# MotorControllerVersion2.net
KiCad netlist of a schematic drawn in EAGLE
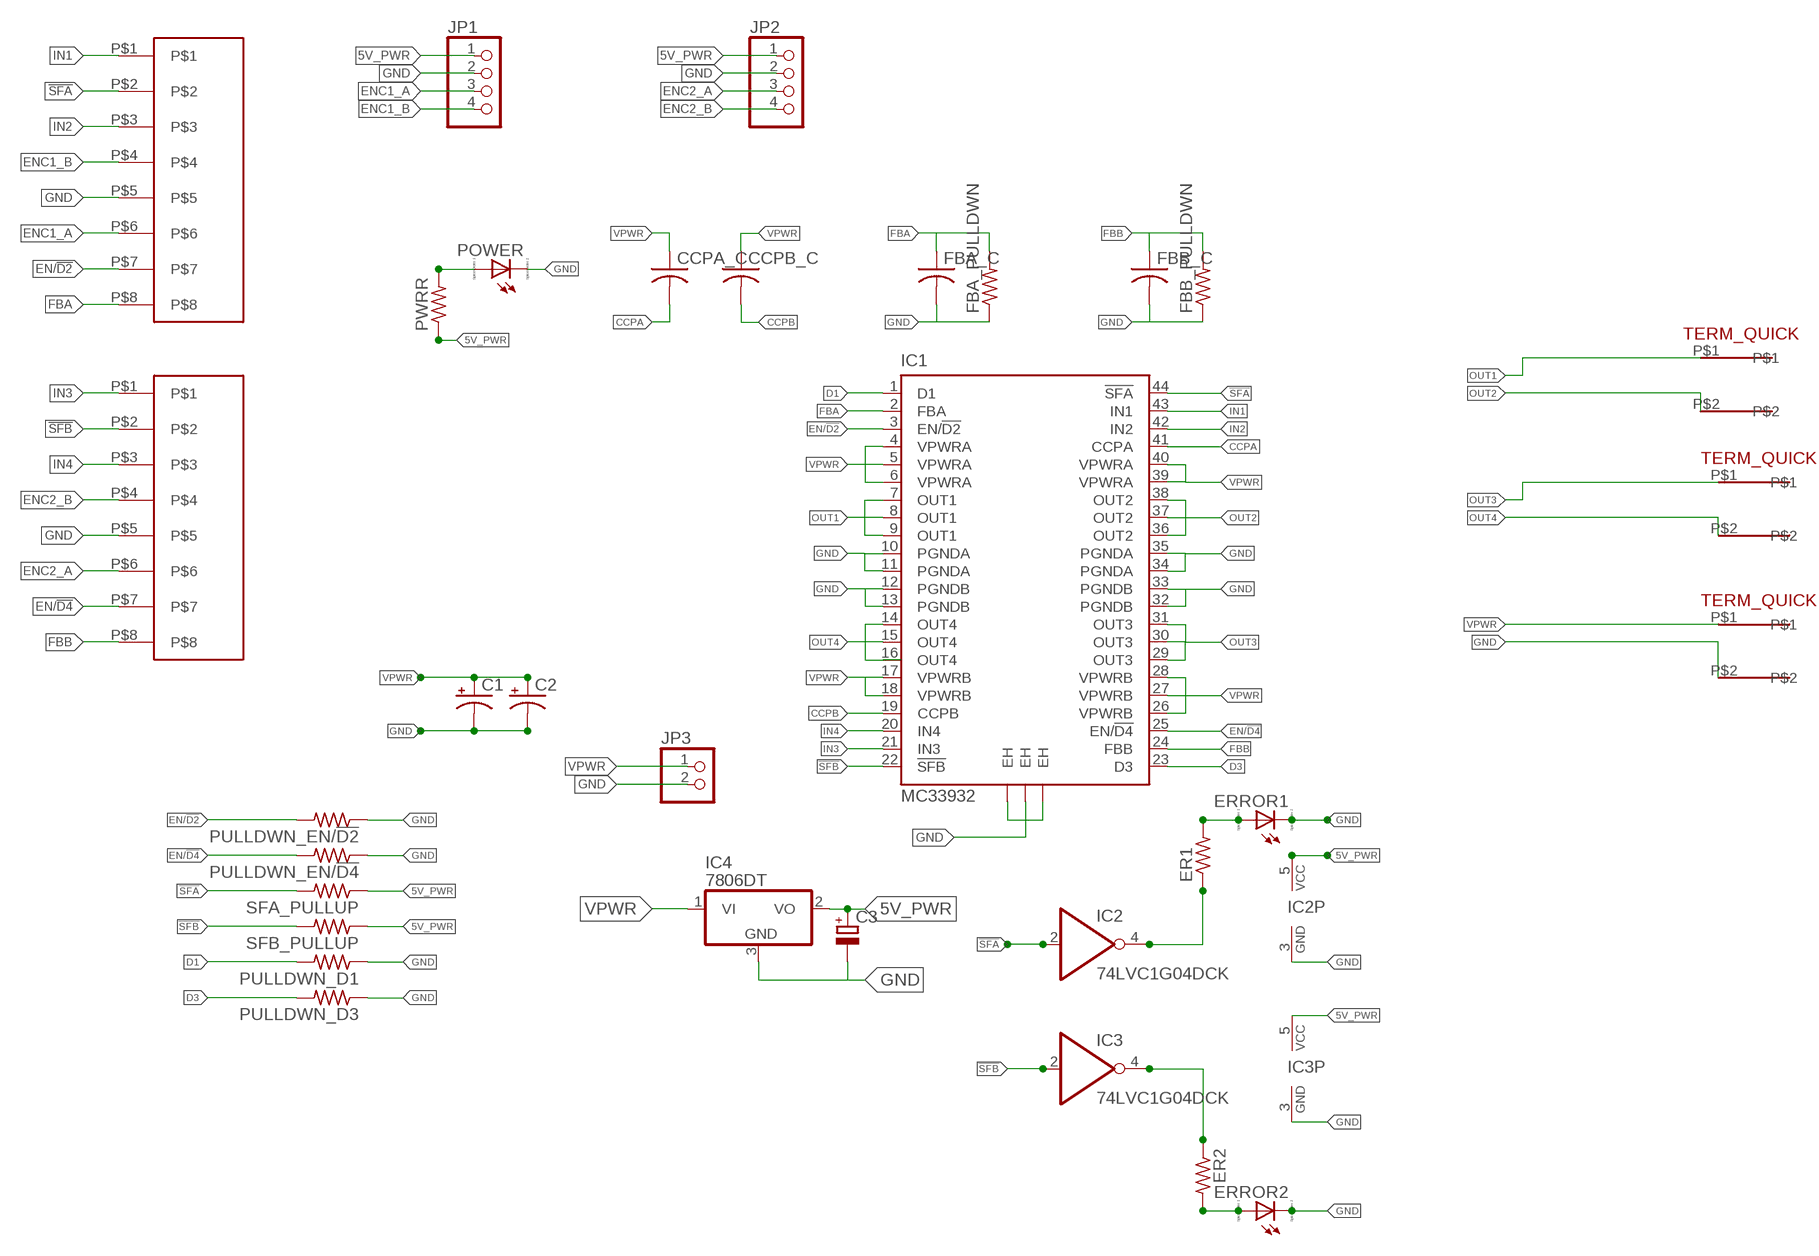
[diagram p0: schematic, sheet 1]

(export (version "E")
  (design (tool "Eeschema 10.0.6"))
  (components
    (comp (ref "C1")
      (value "CPOL-US153CLV-0810")
      (footprint "eagle-import:153CLV-0810")
      (libsource (lib "eagle-import") (part "CPOL-US153CLV-0810"))
    )
    (comp (ref "C2")
      (value "CPOL-US153CLV-0810")
      (footprint "eagle-import:153CLV-0810")
      (libsource (lib "eagle-import") (part "CPOL-US153CLV-0810"))
    )
    (comp (ref "C3")
      (value "CPOL-EU153CLV-0405")
      (footprint "eagle-import:153CLV-0405")
      (libsource (lib "eagle-import") (part "CPOL-EU153CLV-0405"))
    )
    (comp (ref "CCPA_C")
      (value "C-USC0805")
      (footprint "eagle-import:C0805")
      (libsource (lib "eagle-import") (part "C-USC0805"))
    )
    (comp (ref "CCPB_C")
      (value "C-USC0805")
      (footprint "eagle-import:C0805")
      (libsource (lib "eagle-import") (part "C-USC0805"))
    )
    (comp (ref "ER1")
      (value "R-US_R0805")
      (footprint "eagle-import:R0805")
      (libsource (lib "eagle-import") (part "R-US_R0805"))
    )
    (comp (ref "ER2")
      (value "R-US_R0805")
      (footprint "eagle-import:R0805")
      (libsource (lib "eagle-import") (part "R-US_R0805"))
    )
    (comp (ref "ERROR1")
      (value "LED_E")
      (footprint "eagle-import:LED_1206")
      (libsource (lib "eagle-import") (part "LED_E"))
    )
    (comp (ref "ERROR2")
      (value "LED_E")
      (footprint "eagle-import:LED_1206")
      (libsource (lib "eagle-import") (part "LED_E"))
    )
    (comp (ref "FBA_C")
      (value "C-USC0805")
      (footprint "eagle-import:C0805")
      (libsource (lib "eagle-import") (part "C-USC0805"))
    )
    (comp (ref "FBA_PULLDWN")
      (value "R-US_R0805")
      (footprint "eagle-import:R0805")
      (libsource (lib "eagle-import") (part "R-US_R0805"))
    )
    (comp (ref "FBB_C")
      (value "C-USC0805")
      (footprint "eagle-import:C0805")
      (libsource (lib "eagle-import") (part "C-USC0805"))
    )
    (comp (ref "FBB_PULLDWN")
      (value "R-US_R0805")
      (footprint "eagle-import:R0805")
      (libsource (lib "eagle-import") (part "R-US_R0805"))
    )
    (comp (ref "IC1")
      (value "MC33932")
      (footprint "eagle-import:HSOP44")
      (fields (field (name "MPN") "MC33932VW"))
      (libsource (lib "eagle-import") (part "MC33932"))
    )
    (comp (ref "IC2")
      (value "74LVC1G04DCK")
      (footprint "eagle-import:SC70-5")
      (libsource (lib "eagle-import") (part "741G04DCKLVC"))
    )
    (comp (ref "IC3")
      (value "74LVC1G04DCK")
      (footprint "eagle-import:SC70-5")
      (libsource (lib "eagle-import") (part "741G04DCKLVC"))
    )
    (comp (ref "IC4")
      (value "7806DT")
      (footprint "eagle-import:TO252")
      (libsource (lib "eagle-import") (part "78DT06"))
    )
    (comp (ref "JP1")
      (value "PINHD-1X4")
      (footprint "eagle-import:1X04")
      (libsource (lib "eagle-import") (part "PINHD-1X4"))
    )
    (comp (ref "JP2")
      (value "PINHD-1X4")
      (footprint "eagle-import:1X04")
      (libsource (lib "eagle-import") (part "PINHD-1X4"))
    )
    (comp (ref "JP3")
      (value "PINHD-1X2")
      (footprint "eagle-import:1X02")
      (libsource (lib "eagle-import") (part "PINHD-1X2"))
    )
    (comp (ref "POWER")
      (value "LED_E")
      (footprint "eagle-import:LED_1206")
      (libsource (lib "eagle-import") (part "LED_E"))
    )
    (comp (ref "PULLDWN_D1")
      (value "R-US_R0805")
      (footprint "eagle-import:R0805")
      (libsource (lib "eagle-import") (part "R-US_R0805"))
    )
    (comp (ref "PULLDWN_D3")
      (value "R-US_R0805")
      (footprint "eagle-import:R0805")
      (libsource (lib "eagle-import") (part "R-US_R0805"))
    )
    (comp (ref "PULLDWN_EN/!D2")
      (value "R-US_R0805")
      (footprint "eagle-import:R0805")
      (libsource (lib "eagle-import") (part "R-US_R0805"))
    )
    (comp (ref "PULLDWN_EN/!D4")
      (value "R-US_R0805")
      (footprint "eagle-import:R0805")
      (libsource (lib "eagle-import") (part "R-US_R0805"))
    )
    (comp (ref "PWRR")
      (value "R-US_R0805")
      (footprint "eagle-import:R0805")
      (libsource (lib "eagle-import") (part "R-US_R0805"))
    )
    (comp (ref "SFA_PULLUP")
      (value "R-US_R0805")
      (footprint "eagle-import:R0805")
      (libsource (lib "eagle-import") (part "R-US_R0805"))
    )
    (comp (ref "SFB_PULLUP")
      (value "R-US_R0805")
      (footprint "eagle-import:R0805")
      (libsource (lib "eagle-import") (part "R-US_R0805"))
    )
    (comp (ref "U$1")
      (value "ETHERNETPORT")
      (footprint "eagle-import:ETHERNETPORT")
      (libsource (lib "eagle-import") (part "ETHERNETPORT"))
    )
    (comp (ref "U$2")
      (value "ETHERNETPORT")
      (footprint "eagle-import:ETHERNETPORT")
      (libsource (lib "eagle-import") (part "ETHERNETPORT"))
    )
    (comp (ref "U$3")
      (value "TERM_QUICK")
      (footprint "eagle-import:TERM_QUICK")
      (libsource (lib "eagle-import") (part "TERM_QUICK"))
    )
    (comp (ref "U$4")
      (value "TERM_QUICK")
      (footprint "eagle-import:TERM_QUICK")
      (libsource (lib "eagle-import") (part "TERM_QUICK"))
    )
    (comp (ref "U$5")
      (value "TERM_QUICK")
      (footprint "eagle-import:TERM_QUICK")
      (libsource (lib "eagle-import") (part "TERM_QUICK"))
    )
  )
  (nets
    (net (code "1") (name "/EN{slash}~{D2}") (class "Default")
      (node (ref "IC1") (pin "3") (pinfunction "EN/~{D2}_3") (pintype "input"))
      (node (ref "PULLDWN_EN/!D2") (pin "2") (pinfunction "2_2") (pintype "passive"))
      (node (ref "U$1") (pin "P$7") (pinfunction "P$7_P$7") (pintype "bidirectional"))
    )
    (net (code "2") (name "/EN{slash}~{D4}") (class "Default")
      (node (ref "IC1") (pin "25") (pinfunction "EN/~{D4}_25") (pintype "input"))
      (node (ref "PULLDWN_EN/!D4") (pin "2") (pinfunction "2_2") (pintype "passive"))
      (node (ref "U$2") (pin "P$7") (pinfunction "P$7_P$7") (pintype "bidirectional"))
    )
    (net (code "3") (name "/~{SFA}") (class "Default")
      (node (ref "IC1") (pin "44") (pinfunction "~{SFA}_44") (pintype "open_collector"))
      (node (ref "IC2") (pin "2") (pinfunction "I_2") (pintype "input"))
      (node (ref "SFA_PULLUP") (pin "2") (pinfunction "2_2") (pintype "passive"))
      (node (ref "U$1") (pin "P$2") (pinfunction "P$2_P$2") (pintype "bidirectional"))
    )
    (net (code "4") (name "/~{SFB}") (class "Default")
      (node (ref "IC1") (pin "22") (pinfunction "~{SFB}_22") (pintype "open_collector"))
      (node (ref "IC3") (pin "2") (pinfunction "I_2") (pintype "input"))
      (node (ref "SFB_PULLUP") (pin "2") (pinfunction "2_2") (pintype "passive"))
      (node (ref "U$2") (pin "P$2") (pinfunction "P$2_P$2") (pintype "bidirectional"))
    )
    (net (code "5") (name "5V_PWR") (class "Default")
      (node (ref "C3") (pin "+") (pinfunction "+_+") (pintype "passive"))
      (node (ref "IC2") (pin "5") (pinfunction "VCC_5") (pintype "power_in"))
      (node (ref "IC3") (pin "5") (pinfunction "VCC_5") (pintype "power_in"))
      (node (ref "IC4") (pin "2") (pinfunction "VO_2") (pintype "passive"))
      (node (ref "JP1") (pin "1") (pinfunction "1_1") (pintype "passive"))
      (node (ref "JP2") (pin "1") (pinfunction "1_1") (pintype "passive"))
      (node (ref "PWRR") (pin "1") (pinfunction "1_1") (pintype "passive"))
      (node (ref "SFA_PULLUP") (pin "1") (pinfunction "1_1") (pintype "passive"))
      (node (ref "SFB_PULLUP") (pin "1") (pinfunction "1_1") (pintype "passive"))
    )
    (net (code "6") (name "CCPA") (class "Default")
      (node (ref "CCPA_C") (pin "2") (pinfunction "2_2") (pintype "passive"))
      (node (ref "IC1") (pin "41") (pinfunction "CCPA_41") (pintype "output"))
    )
    (net (code "7") (name "CCPB") (class "Default")
      (node (ref "CCPB_C") (pin "2") (pinfunction "2_2") (pintype "passive"))
      (node (ref "IC1") (pin "19") (pinfunction "CCPB_19") (pintype "output"))
    )
    (net (code "8") (name "D1") (class "Default")
      (node (ref "IC1") (pin "1") (pinfunction "D1_1") (pintype "input"))
      (node (ref "PULLDWN_D1") (pin "2") (pinfunction "2_2") (pintype "passive"))
    )
    (net (code "9") (name "D3") (class "Default")
      (node (ref "IC1") (pin "23") (pinfunction "D3_23") (pintype "input"))
      (node (ref "PULLDWN_D3") (pin "2") (pinfunction "2_2") (pintype "passive"))
    )
    (net (code "10") (name "ENC1_A") (class "Default")
      (node (ref "JP1") (pin "3") (pinfunction "3_3") (pintype "passive"))
      (node (ref "U$1") (pin "P$6") (pinfunction "P$6_P$6") (pintype "bidirectional"))
    )
    (net (code "11") (name "ENC1_B") (class "Default")
      (node (ref "JP1") (pin "4") (pinfunction "4_4") (pintype "passive"))
      (node (ref "U$1") (pin "P$4") (pinfunction "P$4_P$4") (pintype "bidirectional"))
    )
    (net (code "12") (name "ENC2_A") (class "Default")
      (node (ref "JP2") (pin "3") (pinfunction "3_3") (pintype "passive"))
      (node (ref "U$2") (pin "P$6") (pinfunction "P$6_P$6") (pintype "bidirectional"))
    )
    (net (code "13") (name "ENC2_B") (class "Default")
      (node (ref "JP2") (pin "4") (pinfunction "4_4") (pintype "passive"))
      (node (ref "U$2") (pin "P$4") (pinfunction "P$4_P$4") (pintype "bidirectional"))
    )
    (net (code "14") (name "FBA") (class "Default")
      (node (ref "FBA_C") (pin "1") (pinfunction "1_1") (pintype "passive"))
      (node (ref "FBA_PULLDWN") (pin "2") (pinfunction "2_2") (pintype "passive"))
      (node (ref "IC1") (pin "2") (pinfunction "FBA_2") (pintype "output"))
      (node (ref "U$1") (pin "P$8") (pinfunction "P$8_P$8") (pintype "bidirectional"))
    )
    (net (code "15") (name "FBB") (class "Default")
      (node (ref "FBB_C") (pin "1") (pinfunction "1_1") (pintype "passive"))
      (node (ref "FBB_PULLDWN") (pin "2") (pinfunction "2_2") (pintype "passive"))
      (node (ref "IC1") (pin "24") (pinfunction "FBB_24") (pintype "output"))
      (node (ref "U$2") (pin "P$8") (pinfunction "P$8_P$8") (pintype "bidirectional"))
    )
    (net (code "16") (name "GND") (class "Default")
      (node (ref "C1") (pin "-") (pinfunction "-_-") (pintype "passive"))
      (node (ref "C2") (pin "-") (pinfunction "-_-") (pintype "passive"))
      (node (ref "C3") (pin "-") (pinfunction "-_-") (pintype "passive"))
      (node (ref "ERROR1") (pin "C") (pinfunction "C_C") (pintype "passive"))
      (node (ref "ERROR2") (pin "C") (pinfunction "C_C") (pintype "passive"))
      (node (ref "FBA_C") (pin "2") (pinfunction "2_2") (pintype "passive"))
      (node (ref "FBA_PULLDWN") (pin "1") (pinfunction "1_1") (pintype "passive"))
      (node (ref "FBB_C") (pin "2") (pinfunction "2_2") (pintype "passive"))
      (node (ref "FBB_PULLDWN") (pin "1") (pinfunction "1_1") (pintype "passive"))
      (node (ref "IC1") (pin "10") (pinfunction "PGNDA_10") (pintype "power_in"))
      (node (ref "IC1") (pin "11") (pinfunction "PGNDA_11") (pintype "power_in"))
      (node (ref "IC1") (pin "12") (pinfunction "PGNDB_12") (pintype "power_in"))
      (node (ref "IC1") (pin "13") (pinfunction "PGNDB_13") (pintype "power_in"))
      (node (ref "IC1") (pin "32") (pinfunction "PGNDB_32") (pintype "power_in"))
      (node (ref "IC1") (pin "33") (pinfunction "PGNDB_33") (pintype "power_in"))
      (node (ref "IC1") (pin "34") (pinfunction "PGNDA_34") (pintype "power_in"))
      (node (ref "IC1") (pin "35") (pinfunction "PGNDA_35") (pintype "power_in"))
      (node (ref "IC1") (pin "EH@1") (pinfunction "EH_EH@1") (pintype "passive"))
      (node (ref "IC1") (pin "EH@2") (pinfunction "EH_EH@2") (pintype "passive"))
      (node (ref "IC1") (pin "EH@3") (pinfunction "EH_EH@3") (pintype "passive"))
      (node (ref "IC2") (pin "3") (pinfunction "GND_3") (pintype "power_in"))
      (node (ref "IC3") (pin "3") (pinfunction "GND_3") (pintype "power_in"))
      (node (ref "IC4") (pin "3") (pinfunction "GND_3") (pintype "passive"))
      (node (ref "JP1") (pin "2") (pinfunction "2_2") (pintype "passive"))
      (node (ref "JP2") (pin "2") (pinfunction "2_2") (pintype "passive"))
      (node (ref "JP3") (pin "2") (pinfunction "2_2") (pintype "passive"))
      (node (ref "POWER") (pin "C") (pinfunction "C_C") (pintype "passive"))
      (node (ref "PULLDWN_D1") (pin "1") (pinfunction "1_1") (pintype "passive"))
      (node (ref "PULLDWN_D3") (pin "1") (pinfunction "1_1") (pintype "passive"))
      (node (ref "PULLDWN_EN/!D2") (pin "1") (pinfunction "1_1") (pintype "passive"))
      (node (ref "PULLDWN_EN/!D4") (pin "1") (pinfunction "1_1") (pintype "passive"))
      (node (ref "U$1") (pin "P$5") (pinfunction "P$5_P$5") (pintype "bidirectional"))
      (node (ref "U$2") (pin "P$5") (pinfunction "P$5_P$5") (pintype "bidirectional"))
      (node (ref "U$5") (pin "P$2") (pinfunction "P$2_P$2") (pintype "bidirectional"))
    )
    (net (code "17") (name "IN1") (class "Default")
      (node (ref "IC1") (pin "43") (pinfunction "IN1_43") (pintype "input"))
      (node (ref "U$1") (pin "P$1") (pinfunction "P$1_P$1") (pintype "bidirectional"))
    )
    (net (code "18") (name "IN2") (class "Default")
      (node (ref "IC1") (pin "42") (pinfunction "IN2_42") (pintype "input"))
      (node (ref "U$1") (pin "P$3") (pinfunction "P$3_P$3") (pintype "bidirectional"))
    )
    (net (code "19") (name "IN3") (class "Default")
      (node (ref "IC1") (pin "21") (pinfunction "IN3_21") (pintype "input"))
      (node (ref "U$2") (pin "P$1") (pinfunction "P$1_P$1") (pintype "bidirectional"))
    )
    (net (code "20") (name "IN4") (class "Default")
      (node (ref "IC1") (pin "20") (pinfunction "IN4_20") (pintype "input"))
      (node (ref "U$2") (pin "P$3") (pinfunction "P$3_P$3") (pintype "bidirectional"))
    )
    (net (code "21") (name "Net-(ER1-Pad2)") (class "Default")
      (node (ref "ER1") (pin "2") (pinfunction "2_2") (pintype "passive"))
      (node (ref "ERROR1") (pin "A") (pinfunction "A_A") (pintype "passive"))
    )
    (net (code "22") (name "Net-(ER2-Pad2)") (class "Default")
      (node (ref "ER2") (pin "2") (pinfunction "2_2") (pintype "passive"))
      (node (ref "ERROR2") (pin "A") (pinfunction "A_A") (pintype "passive"))
    )
    (net (code "23") (name "Net-(IC2A-O)") (class "Default")
      (node (ref "ER1") (pin "1") (pinfunction "1_1") (pintype "passive"))
      (node (ref "IC2") (pin "4") (pinfunction "O_4") (pintype "output"))
    )
    (net (code "24") (name "Net-(IC3A-O)") (class "Default")
      (node (ref "ER2") (pin "1") (pinfunction "1_1") (pintype "passive"))
      (node (ref "IC3") (pin "4") (pinfunction "O_4") (pintype "output"))
    )
    (net (code "25") (name "Net-(POWER-PadA)") (class "Default")
      (node (ref "POWER") (pin "A") (pinfunction "A_A") (pintype "passive"))
      (node (ref "PWRR") (pin "2") (pinfunction "2_2") (pintype "passive"))
    )
    (net (code "26") (name "OUT1") (class "Default")
      (node (ref "IC1") (pin "7") (pinfunction "OUT1_7") (pintype "output"))
      (node (ref "IC1") (pin "8") (pinfunction "OUT1_8") (pintype "passive"))
      (node (ref "IC1") (pin "9") (pinfunction "OUT1_9") (pintype "passive"))
      (node (ref "U$3") (pin "P$1") (pinfunction "P$1_P$1") (pintype "bidirectional"))
    )
    (net (code "27") (name "OUT2") (class "Default")
      (node (ref "IC1") (pin "36") (pinfunction "OUT2_36") (pintype "output"))
      (node (ref "IC1") (pin "37") (pinfunction "OUT2_37") (pintype "passive"))
      (node (ref "IC1") (pin "38") (pinfunction "OUT2_38") (pintype "passive"))
      (node (ref "U$3") (pin "P$2") (pinfunction "P$2_P$2") (pintype "bidirectional"))
    )
    (net (code "28") (name "OUT3") (class "Default")
      (node (ref "IC1") (pin "29") (pinfunction "OUT3_29") (pintype "output"))
      (node (ref "IC1") (pin "30") (pinfunction "OUT3_30") (pintype "passive"))
      (node (ref "IC1") (pin "31") (pinfunction "OUT3_31") (pintype "passive"))
      (node (ref "U$4") (pin "P$1") (pinfunction "P$1_P$1") (pintype "bidirectional"))
    )
    (net (code "29") (name "OUT4") (class "Default")
      (node (ref "IC1") (pin "14") (pinfunction "OUT4_14") (pintype "output"))
      (node (ref "IC1") (pin "15") (pinfunction "OUT4_15") (pintype "passive"))
      (node (ref "IC1") (pin "16") (pinfunction "OUT4_16") (pintype "passive"))
      (node (ref "U$4") (pin "P$2") (pinfunction "P$2_P$2") (pintype "bidirectional"))
    )
    (net (code "30") (name "VPWR") (class "Default")
      (node (ref "C1") (pin "+") (pinfunction "+_+") (pintype "passive"))
      (node (ref "C2") (pin "+") (pinfunction "+_+") (pintype "passive"))
      (node (ref "CCPA_C") (pin "1") (pinfunction "1_1") (pintype "passive"))
      (node (ref "CCPB_C") (pin "1") (pinfunction "1_1") (pintype "passive"))
      (node (ref "IC1") (pin "17") (pinfunction "VPWRB_17") (pintype "input"))
      (node (ref "IC1") (pin "18") (pinfunction "VPWRB_18") (pintype "input"))
      (node (ref "IC1") (pin "26") (pinfunction "VPWRB_26") (pintype "input"))
      (node (ref "IC1") (pin "27") (pinfunction "VPWRB_27") (pintype "input"))
      (node (ref "IC1") (pin "28") (pinfunction "VPWRB_28") (pintype "input"))
      (node (ref "IC1") (pin "39") (pinfunction "VPWRA_39") (pintype "input"))
      (node (ref "IC1") (pin "4") (pinfunction "VPWRA_4") (pintype "input"))
      (node (ref "IC1") (pin "40") (pinfunction "VPWRA_40") (pintype "input"))
      (node (ref "IC1") (pin "5") (pinfunction "VPWRA_5") (pintype "input"))
      (node (ref "IC1") (pin "6") (pinfunction "VPWRA_6") (pintype "input"))
      (node (ref "IC4") (pin "1") (pinfunction "VI_1") (pintype "input"))
      (node (ref "JP3") (pin "1") (pinfunction "1_1") (pintype "passive"))
      (node (ref "U$5") (pin "P$1") (pinfunction "P$1_P$1") (pintype "bidirectional"))
    )
  )
)
